# WirelessTRV.net
KiCad netlist of a schematic drawn in EAGLE
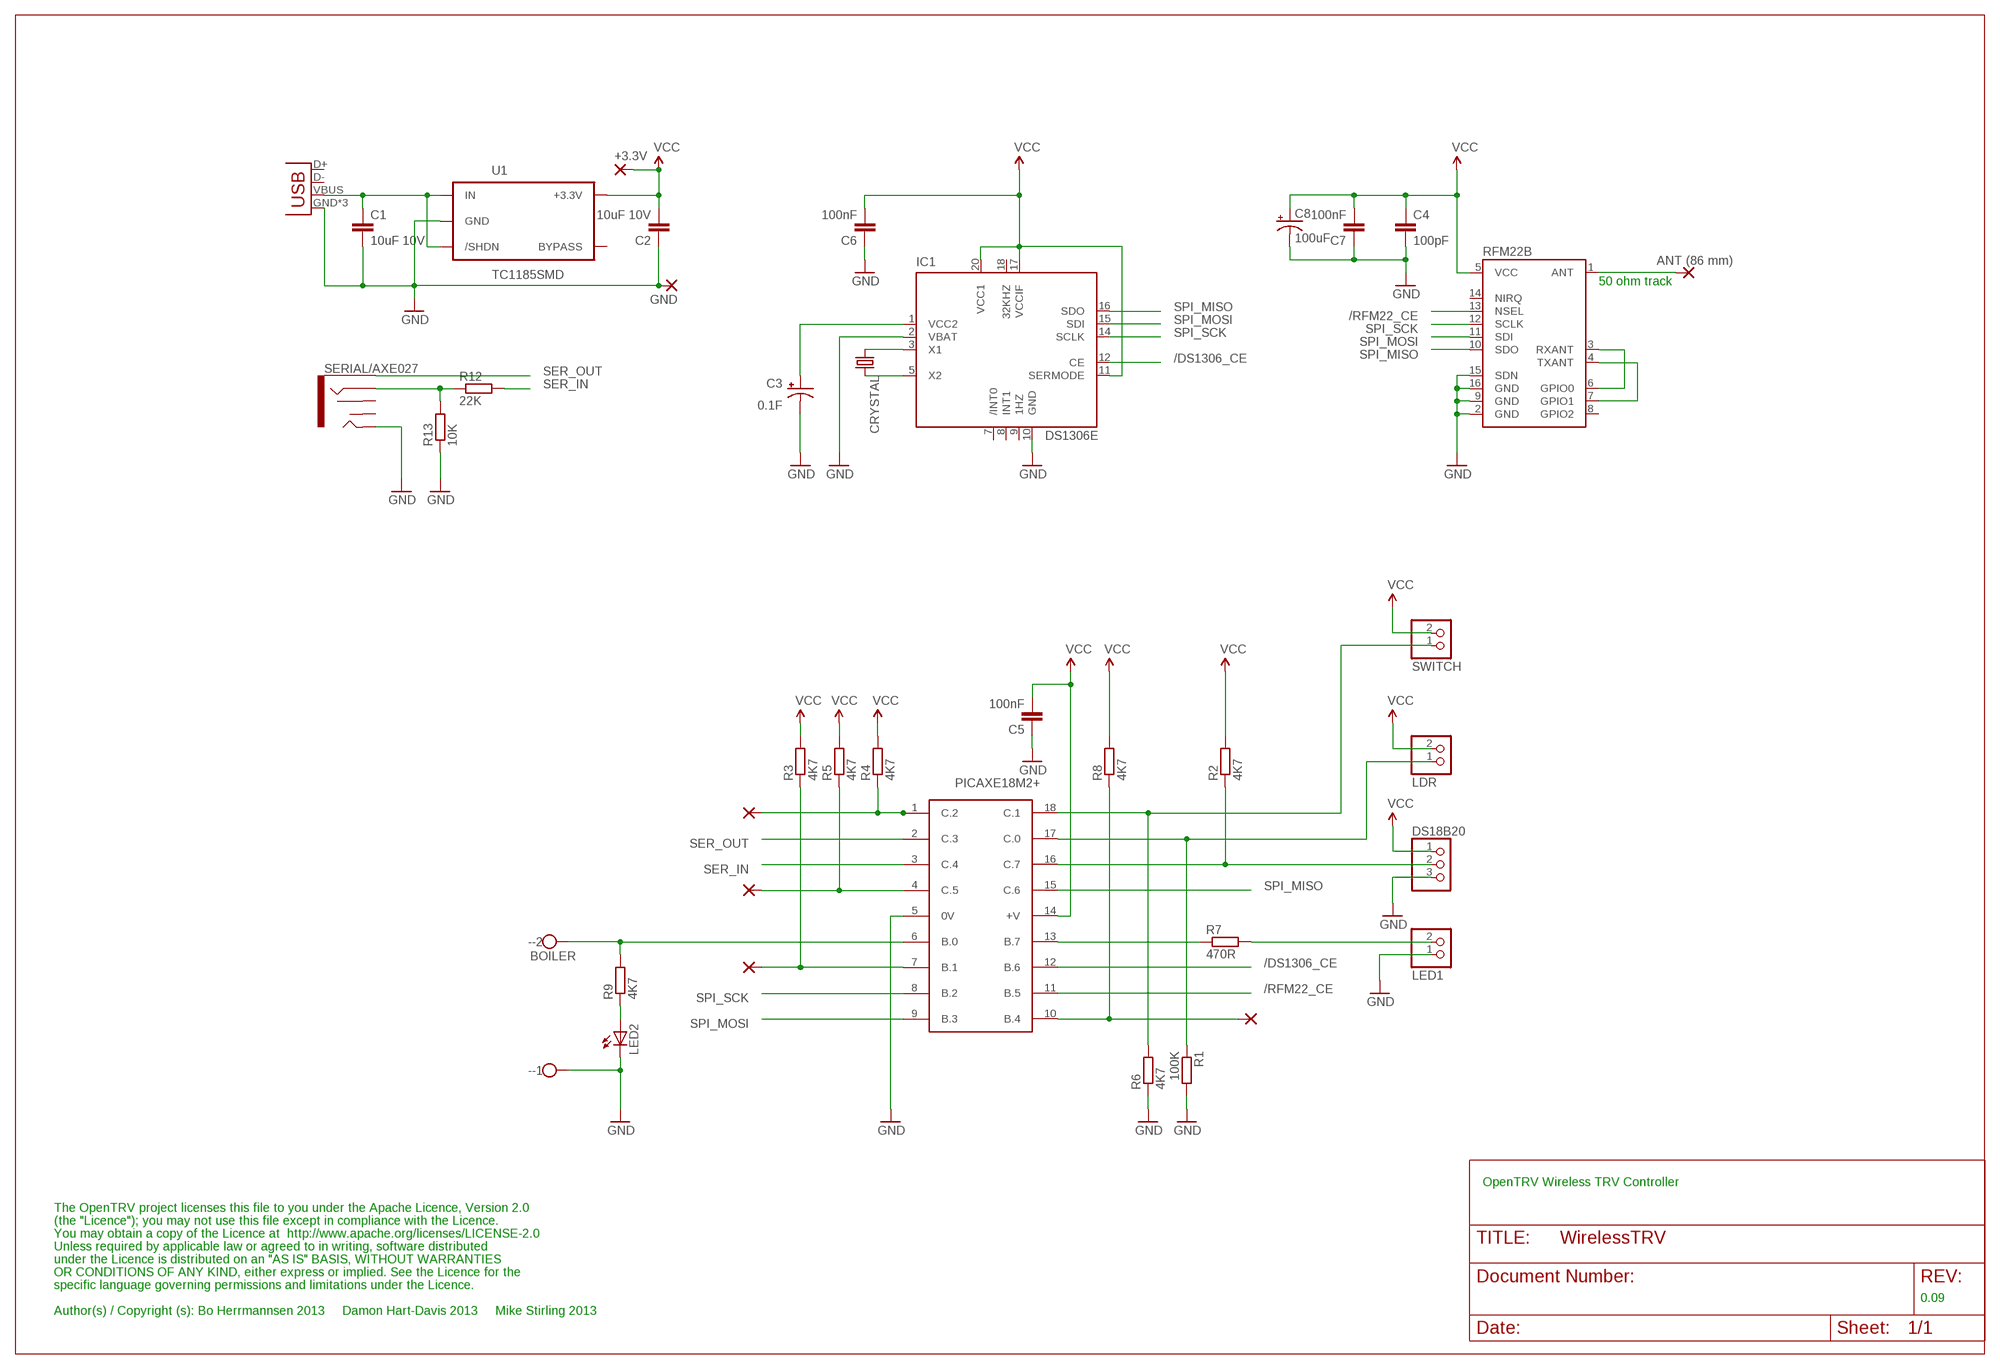
[diagram p0: schematic, sheet 1]

(export (version "E")
  (design (tool "Eeschema 10.0.6"))
  (components
    (comp (ref "+3.3V")
      (value "2,15/1,0")
      (footprint "eagle-import:2,15_1,0")
      (libsource (lib "eagle-import") (part "2,15/1,0"))
    )
    (comp (ref "-")
      (value "BOILER")
      (footprint "eagle-import:W237-102")
      (fields (field (name "MPN") "237-102"))
      (libsource (lib "eagle-import") (part "W237-102"))
    )
    (comp (ref "1")
      (value "2,15/1,0")
      (footprint "eagle-import:2,15_1,0")
      (libsource (lib "eagle-import") (part "2,15/1,0"))
    )
    (comp (ref "4")
      (value "2,15/1,0")
      (footprint "eagle-import:2,15_1,0")
      (libsource (lib "eagle-import") (part "2,15/1,0"))
    )
    (comp (ref "5V")
      (value "USB-MICROB")
      (footprint "eagle-import:USB-MICROB")
      (libsource (lib "eagle-import") (part "USB-MICROB"))
    )
    (comp (ref "7")
      (value "2,15/1,0")
      (footprint "eagle-import:2,15_1,0")
      (libsource (lib "eagle-import") (part "2,15/1,0"))
    )
    (comp (ref "10")
      (value "2,15/1,0")
      (footprint "eagle-import:2,15_1,0")
      (libsource (lib "eagle-import") (part "2,15/1,0"))
    )
    (comp (ref "ANT")
      (value "ANT (86 mm)")
      (footprint "eagle-import:2,15_1,0")
      (libsource (lib "eagle-import") (part "2,15/1,0"))
    )
    (comp (ref "C1")
      (value "10uF 10V")
      (footprint "eagle-import:0603-CAP")
      (libsource (lib "eagle-import") (part "CAP0603-CAP"))
    )
    (comp (ref "C2")
      (value "10uF 10V")
      (footprint "eagle-import:0603-CAP")
      (libsource (lib "eagle-import") (part "CAP0603-CAP"))
    )
    (comp (ref "C3")
      (value "0.1F")
      (footprint "eagle-import:SUPERCAP3.6V")
      (libsource (lib "eagle-import") (part "SUPERCAP3.6VSUPERCAP3.6V"))
    )
    (comp (ref "C4")
      (value "100pF")
      (footprint "eagle-import:0603-CAP")
      (libsource (lib "eagle-import") (part "CAP0603-CAP"))
    )
    (comp (ref "C5")
      (value "100nF")
      (footprint "eagle-import:0603-CAP")
      (libsource (lib "eagle-import") (part "CAP0603-CAP"))
    )
    (comp (ref "C6")
      (value "100nF")
      (footprint "eagle-import:0603-CAP")
      (libsource (lib "eagle-import") (part "CAP0603-CAP"))
    )
    (comp (ref "C7")
      (value "100nF")
      (footprint "eagle-import:0603-CAP")
      (libsource (lib "eagle-import") (part "CAP0603-CAP"))
    )
    (comp (ref "C8")
      (value "100uF")
      (footprint "eagle-import:EIA3216")
      (libsource (lib "eagle-import") (part "CAP_POL1206"))
    )
    (comp (ref "CRYSTAL")
      (value "MC-306")
      (footprint "eagle-import:MC-306")
      (fields (field (name "MPN") "MC-306 60.0KHZ  100PPM ,12.5PF"))
      (libsource (lib "eagle-import") (part "MC-306"))
    )
    (comp (ref "DS18B20")
      (value "PINHD-1X3")
      (footprint "eagle-import:1X03")
      (libsource (lib "eagle-import") (part "PINHD-1X3"))
    )
    (comp (ref "GND")
      (value "2,15/1,0")
      (footprint "eagle-import:2,15_1,0")
      (libsource (lib "eagle-import") (part "2,15/1,0"))
    )
    (comp (ref "IC1")
      (value "DS1306E")
      (footprint "eagle-import:TSSOP20")
      (libsource (lib "eagle-import") (part "DS1306E"))
    )
    (comp (ref "LDR")
      (value "PINHD-1X2")
      (footprint "eagle-import:1X02")
      (libsource (lib "eagle-import") (part "PINHD-1X2"))
    )
    (comp (ref "LED1")
      (value "PINHD-1X2")
      (footprint "eagle-import:1X02")
      (libsource (lib "eagle-import") (part "PINHD-1X2"))
    )
    (comp (ref "LED2")
      (value "LED2012")
      (footprint "eagle-import:LED2012")
      (libsource (lib "eagle-import") (part "LED2012"))
    )
    (comp (ref "PICAXE18M2+")
      (value "PICAXE18M2SO")
      (footprint "eagle-import:SO-18W")
      (libsource (lib "eagle-import") (part "PICAXE18M2SO"))
    )
    (comp (ref "R1")
      (value "100K")
      (footprint "eagle-import:R0603")
      (libsource (lib "eagle-import") (part "R-EU_R0603"))
    )
    (comp (ref "R2")
      (value "4K7")
      (footprint "eagle-import:R0603")
      (libsource (lib "eagle-import") (part "R-EU_R0603"))
    )
    (comp (ref "R3")
      (value "4K7")
      (footprint "eagle-import:R0603")
      (libsource (lib "eagle-import") (part "R-EU_R0603"))
    )
    (comp (ref "R4")
      (value "4K7")
      (footprint "eagle-import:R0603")
      (libsource (lib "eagle-import") (part "R-EU_R0603"))
    )
    (comp (ref "R5")
      (value "4K7")
      (footprint "eagle-import:R0603")
      (libsource (lib "eagle-import") (part "R-EU_R0603"))
    )
    (comp (ref "R6")
      (value "4K7")
      (footprint "eagle-import:R0603")
      (libsource (lib "eagle-import") (part "R-EU_R0603"))
    )
    (comp (ref "R7")
      (value "470R")
      (footprint "eagle-import:R0603")
      (libsource (lib "eagle-import") (part "R-EU_R0603"))
    )
    (comp (ref "R8")
      (value "4K7")
      (footprint "eagle-import:R0603")
      (libsource (lib "eagle-import") (part "R-EU_R0603"))
    )
    (comp (ref "R9")
      (value "4K7")
      (footprint "eagle-import:R0603")
      (libsource (lib "eagle-import") (part "R-EU_R0603"))
    )
    (comp (ref "R12")
      (value "22K")
      (footprint "eagle-import:R0603")
      (libsource (lib "eagle-import") (part "R-EU_R0603"))
    )
    (comp (ref "R13")
      (value "10K")
      (footprint "eagle-import:R0603")
      (libsource (lib "eagle-import") (part "R-EU_R0603"))
    )
    (comp (ref "RFM22B")
      (value "RFM22SMD")
      (footprint "eagle-import:RFM22-XXX-S2")
      (libsource (lib "eagle-import") (part "RFM22SMD"))
    )
    (comp (ref "SERIAL/AXE027")
      (value "AUDIO-JACK2SMD")
      (footprint "eagle-import:AUDIO-JACK-3.5MM-SMD")
      (libsource (lib "eagle-import") (part "AUDIO-JACK2SMD"))
    )
    (comp (ref "SWITCH")
      (value "PINHD-1X2")
      (footprint "eagle-import:1X02")
      (libsource (lib "eagle-import") (part "PINHD-1X2"))
    )
    (comp (ref "U1")
      (value "TC1185SMD")
      (footprint "eagle-import:TC1185")
      (libsource (lib "eagle-import") (part "TC1185SMD"))
    )
  )
  (nets
    (net (code "1") (name "/SER_IN") (class "Default")
      (node (ref "PICAXE18M2+") (pin "3") (pinfunction "C.4_3") (pintype "bidirectional"))
      (node (ref "R12") (pin "2") (pinfunction "2_2") (pintype "passive"))
    )
    (net (code "2") (name "/SER_OUT") (class "Default")
      (node (ref "PICAXE18M2+") (pin "2") (pinfunction "C.3_2") (pintype "bidirectional"))
      (node (ref "SERIAL/AXE027") (pin "SLEEVE") (pinfunction "SLEEVE_SLEEVE") (pintype "bidirectional"))
    )
    (net (code "3") (name "/SPI_MISO") (class "Default")
      (node (ref "IC1") (pin "16") (pinfunction "SDO_16") (pintype "output"))
      (node (ref "PICAXE18M2+") (pin "15") (pinfunction "C.6_15") (pintype "bidirectional"))
      (node (ref "RFM22B") (pin "10") (pinfunction "SDO_10") (pintype "output"))
    )
    (net (code "4") (name "/SPI_MOSI") (class "Default")
      (node (ref "IC1") (pin "15") (pinfunction "SDI_15") (pintype "input"))
      (node (ref "PICAXE18M2+") (pin "9") (pinfunction "B.3_9") (pintype "bidirectional"))
      (node (ref "RFM22B") (pin "11") (pinfunction "SDI_11") (pintype "input"))
    )
    (net (code "5") (name "/SPI_SCK") (class "Default")
      (node (ref "IC1") (pin "14") (pinfunction "SCLK_14") (pintype "input"))
      (node (ref "PICAXE18M2+") (pin "8") (pinfunction "B.2_8") (pintype "bidirectional"))
      (node (ref "RFM22B") (pin "12") (pinfunction "SCLK_12") (pintype "input"))
    )
    (net (code "6") (name "/{slash}DS1306_CE") (class "Default")
      (node (ref "IC1") (pin "12") (pinfunction "CE_12") (pintype "input"))
      (node (ref "PICAXE18M2+") (pin "12") (pinfunction "B.6_12") (pintype "bidirectional"))
    )
    (net (code "7") (name "/{slash}RFM22_CE") (class "Default")
      (node (ref "PICAXE18M2+") (pin "11") (pinfunction "B.5_11") (pintype "bidirectional"))
      (node (ref "RFM22B") (pin "13") (pinfunction "NSEL_13") (pintype "input"))
    )
    (net (code "8") (name "GND") (class "Default")
      (node (ref "-") (pin "1") (pinfunction "KL_1") (pintype "passive"))
      (node (ref "5V") (pin "GND") (pinfunction "GND_GND") (pintype "bidirectional"))
      (node (ref "5V") (pin "MT1") (pinfunction "GND_MT1") (pintype "bidirectional"))
      (node (ref "5V") (pin "MT2") (pinfunction "GND_MT2") (pintype "bidirectional"))
      (node (ref "C1") (pin "2") (pinfunction "2_2") (pintype "passive"))
      (node (ref "C2") (pin "1") (pinfunction "1_1") (pintype "passive"))
      (node (ref "C3") (pin "-") (pinfunction "-_-") (pintype "passive"))
      (node (ref "C4") (pin "2") (pinfunction "2_2") (pintype "passive"))
      (node (ref "C5") (pin "1") (pinfunction "1_1") (pintype "passive"))
      (node (ref "C6") (pin "1") (pinfunction "1_1") (pintype "passive"))
      (node (ref "C7") (pin "1") (pinfunction "1_1") (pintype "passive"))
      (node (ref "C8") (pin "C") (pinfunction "-_C") (pintype "passive"))
      (node (ref "DS18B20") (pin "3") (pinfunction "3_3") (pintype "passive"))
      (node (ref "GND") (pin "1") (pinfunction "P_1") (pintype "passive"))
      (node (ref "IC1") (pin "10") (pinfunction "GND_10") (pintype "power_in"))
      (node (ref "IC1") (pin "2") (pinfunction "VBAT_2") (pintype "power_in"))
      (node (ref "LED1") (pin "1") (pinfunction "1_1") (pintype "passive"))
      (node (ref "LED2") (pin "2") (pinfunction "C_2") (pintype "passive"))
      (node (ref "PICAXE18M2+") (pin "5") (pinfunction "0V_5") (pintype "power_in"))
      (node (ref "R1") (pin "2") (pinfunction "2_2") (pintype "passive"))
      (node (ref "R13") (pin "1") (pinfunction "1_1") (pintype "passive"))
      (node (ref "R6") (pin "1") (pinfunction "1_1") (pintype "passive"))
      (node (ref "RFM22B") (pin "15") (pinfunction "SDN_15") (pintype "input"))
      (node (ref "RFM22B") (pin "16") (pinfunction "GND_16") (pintype "power_in"))
      (node (ref "RFM22B") (pin "2") (pinfunction "GND_2") (pintype "power_in"))
      (node (ref "RFM22B") (pin "9") (pinfunction "GND_9") (pintype "power_in"))
      (node (ref "SERIAL/AXE027") (pin "TIP") (pinfunction "TIP_TIP") (pintype "bidirectional"))
      (node (ref "U1") (pin "2") (pinfunction "GND_2") (pintype "passive"))
    )
    (net (code "9") (name "Net-(-B-KL)") (class "Default")
      (node (ref "-") (pin "2") (pinfunction "KL_2") (pintype "passive"))
      (node (ref "PICAXE18M2+") (pin "6") (pinfunction "B.0_6") (pintype "bidirectional"))
      (node (ref "R9") (pin "2") (pinfunction "2_2") (pintype "passive"))
    )
    (net (code "10") (name "Net-(1-P)") (class "Default")
      (node (ref "1") (pin "1") (pinfunction "P_1") (pintype "passive"))
      (node (ref "PICAXE18M2+") (pin "1") (pinfunction "C.2_1") (pintype "bidirectional"))
      (node (ref "R4") (pin "1") (pinfunction "1_1") (pintype "passive"))
    )
    (net (code "11") (name "Net-(4-P)") (class "Default")
      (node (ref "4") (pin "1") (pinfunction "P_1") (pintype "passive"))
      (node (ref "PICAXE18M2+") (pin "4") (pinfunction "C.5_4") (pintype "bidirectional"))
      (node (ref "R5") (pin "1") (pinfunction "1_1") (pintype "passive"))
    )
    (net (code "12") (name "Net-(7-P)") (class "Default")
      (node (ref "7") (pin "1") (pinfunction "P_1") (pintype "passive"))
      (node (ref "PICAXE18M2+") (pin "7") (pinfunction "B.1_7") (pintype "bidirectional"))
      (node (ref "R3") (pin "1") (pinfunction "1_1") (pintype "passive"))
    )
    (net (code "13") (name "Net-(10-P)") (class "Default")
      (node (ref "10") (pin "1") (pinfunction "P_1") (pintype "passive"))
      (node (ref "PICAXE18M2+") (pin "10") (pinfunction "B.4_10") (pintype "bidirectional"))
      (node (ref "R8") (pin "1") (pinfunction "1_1") (pintype "passive"))
    )
    (net (code "14") (name "Net-(ANT-P)") (class "Default")
      (node (ref "ANT") (pin "1") (pinfunction "P_1") (pintype "passive"))
      (node (ref "RFM22B") (pin "1") (pinfunction "ANT_1") (pintype "bidirectional"))
    )
    (net (code "15") (name "Net-(CRYSTAL-2)") (class "Default")
      (node (ref "CRYSTAL") (pin "4") (pinfunction "2_4") (pintype "passive"))
      (node (ref "IC1") (pin "5") (pinfunction "X2_5") (pintype "input"))
    )
    (net (code "16") (name "Net-(IC1-VCC2)") (class "Default")
      (node (ref "C3") (pin "+") (pinfunction "+_+") (pintype "passive"))
      (node (ref "IC1") (pin "1") (pinfunction "VCC2_1") (pintype "power_in"))
    )
    (net (code "17") (name "Net-(IC1-X1)") (class "Default")
      (node (ref "CRYSTAL") (pin "1") (pinfunction "1_1") (pintype "passive"))
      (node (ref "IC1") (pin "3") (pinfunction "X1_3") (pintype "input"))
    )
    (net (code "18") (name "Net-(LED1-Pad2)") (class "Default")
      (node (ref "LED1") (pin "2") (pinfunction "2_2") (pintype "passive"))
      (node (ref "R7") (pin "2") (pinfunction "2_2") (pintype "passive"))
    )
    (net (code "19") (name "Net-(LED2-A)") (class "Default")
      (node (ref "LED2") (pin "1") (pinfunction "A_1") (pintype "passive"))
      (node (ref "R9") (pin "1") (pinfunction "1_1") (pintype "passive"))
    )
    (net (code "20") (name "Net-(PICAXE18M2+-B.7)") (class "Default")
      (node (ref "PICAXE18M2+") (pin "13") (pinfunction "B.7_13") (pintype "bidirectional"))
      (node (ref "R7") (pin "1") (pinfunction "1_1") (pintype "passive"))
    )
    (net (code "21") (name "Net-(PICAXE18M2+-C.0)") (class "Default")
      (node (ref "LDR") (pin "1") (pinfunction "1_1") (pintype "passive"))
      (node (ref "PICAXE18M2+") (pin "17") (pinfunction "C.0_17") (pintype "bidirectional"))
      (node (ref "R1") (pin "1") (pinfunction "1_1") (pintype "passive"))
    )
    (net (code "22") (name "Net-(PICAXE18M2+-C.1)") (class "Default")
      (node (ref "PICAXE18M2+") (pin "18") (pinfunction "C.1_18") (pintype "bidirectional"))
      (node (ref "R6") (pin "2") (pinfunction "2_2") (pintype "passive"))
      (node (ref "SWITCH") (pin "1") (pinfunction "1_1") (pintype "passive"))
    )
    (net (code "23") (name "Net-(PICAXE18M2+-C.7)") (class "Default")
      (node (ref "DS18B20") (pin "2") (pinfunction "2_2") (pintype "passive"))
      (node (ref "PICAXE18M2+") (pin "16") (pinfunction "C.7_16") (pintype "bidirectional"))
      (node (ref "R2") (pin "1") (pinfunction "1_1") (pintype "passive"))
    )
    (net (code "24") (name "Net-(R12-Pad1)") (class "Default")
      (node (ref "R12") (pin "1") (pinfunction "1_1") (pintype "passive"))
      (node (ref "R13") (pin "2") (pinfunction "2_2") (pintype "passive"))
      (node (ref "SERIAL/AXE027") (pin "RING") (pinfunction "RING_RING") (pintype "bidirectional"))
    )
    (net (code "25") (name "Net-(RFM22B-GPIO0)") (class "Default")
      (node (ref "RFM22B") (pin "3") (pinfunction "RXANT_3") (pintype "input"))
      (node (ref "RFM22B") (pin "6") (pinfunction "GPIO0_6") (pintype "bidirectional"))
    )
    (net (code "26") (name "Net-(RFM22B-GPIO1)") (class "Default")
      (node (ref "RFM22B") (pin "4") (pinfunction "TXANT_4") (pintype "input"))
      (node (ref "RFM22B") (pin "7") (pinfunction "GPIO1_7") (pintype "bidirectional"))
    )
    (net (code "27") (name "Net-(U1-IN)") (class "Default")
      (node (ref "5V") (pin "VBUS") (pinfunction "VBUS_VBUS") (pintype "bidirectional"))
      (node (ref "C1") (pin "1") (pinfunction "1_1") (pintype "passive"))
      (node (ref "U1") (pin "1") (pinfunction "IN_1") (pintype "passive"))
      (node (ref "U1") (pin "3") (pinfunction "/SHDN_3") (pintype "passive"))
    )
    (net (code "28") (name "VCC") (class "Default")
      (node (ref "+3.3V") (pin "1") (pinfunction "P_1") (pintype "passive"))
      (node (ref "C2") (pin "2") (pinfunction "2_2") (pintype "passive"))
      (node (ref "C4") (pin "1") (pinfunction "1_1") (pintype "passive"))
      (node (ref "C5") (pin "2") (pinfunction "2_2") (pintype "passive"))
      (node (ref "C6") (pin "2") (pinfunction "2_2") (pintype "passive"))
      (node (ref "C7") (pin "2") (pinfunction "2_2") (pintype "passive"))
      (node (ref "C8") (pin "A") (pinfunction "+_A") (pintype "passive"))
      (node (ref "DS18B20") (pin "1") (pinfunction "1_1") (pintype "passive"))
      (node (ref "IC1") (pin "11") (pinfunction "SERMODE_11") (pintype "input"))
      (node (ref "IC1") (pin "17") (pinfunction "VCCIF_17") (pintype "power_in"))
      (node (ref "IC1") (pin "20") (pinfunction "VCC1_20") (pintype "power_in"))
      (node (ref "LDR") (pin "2") (pinfunction "2_2") (pintype "passive"))
      (node (ref "PICAXE18M2+") (pin "14") (pinfunction "+V_14") (pintype "power_in"))
      (node (ref "R2") (pin "2") (pinfunction "2_2") (pintype "passive"))
      (node (ref "R3") (pin "2") (pinfunction "2_2") (pintype "passive"))
      (node (ref "R4") (pin "2") (pinfunction "2_2") (pintype "passive"))
      (node (ref "R5") (pin "2") (pinfunction "2_2") (pintype "passive"))
      (node (ref "R8") (pin "2") (pinfunction "2_2") (pintype "passive"))
      (node (ref "RFM22B") (pin "5") (pinfunction "VCC_5") (pintype "bidirectional"))
      (node (ref "SWITCH") (pin "2") (pinfunction "2_2") (pintype "passive"))
      (node (ref "U1") (pin "5") (pinfunction "+3.3V_5") (pintype "power_in"))
    )
    (net (code "29") (name "unconnected-(5V-PadD+)") (class "Default")
      (node (ref "5V") (pin "D+") (pinfunction "D+_D+") (pintype "bidirectional"))
    )
    (net (code "30") (name "unconnected-(5V-PadD-)") (class "Default")
      (node (ref "5V") (pin "D-") (pinfunction "D-_D-") (pintype "bidirectional"))
    )
    (net (code "31") (name "unconnected-(IC1-1HZ-Pad9)") (class "Default")
      (node (ref "IC1") (pin "9") (pinfunction "1HZ_9") (pintype "output"))
    )
    (net (code "32") (name "unconnected-(IC1-32KHZ-Pad18)") (class "Default")
      (node (ref "IC1") (pin "18") (pinfunction "32KHZ_18") (pintype "output"))
    )
    (net (code "33") (name "unconnected-(IC1-INT1-Pad8)") (class "Default")
      (node (ref "IC1") (pin "8") (pinfunction "INT1_8") (pintype "output"))
    )
    (net (code "34") (name "unconnected-(IC1-{slash}INT0-Pad7)") (class "Default")
      (node (ref "IC1") (pin "7") (pinfunction "/INT0_7") (pintype "output"))
    )
    (net (code "35") (name "unconnected-(RFM22B-GPIO2-Pad8)") (class "Default")
      (node (ref "RFM22B") (pin "8") (pinfunction "GPIO2_8") (pintype "bidirectional"))
    )
    (net (code "36") (name "unconnected-(RFM22B-NIRQ-Pad14)") (class "Default")
      (node (ref "RFM22B") (pin "14") (pinfunction "NIRQ_14") (pintype "output"))
    )
    (net (code "37") (name "unconnected-(SERIAL/AXE027-PadRSH)") (class "Default")
      (node (ref "SERIAL/AXE027") (pin "RSH") (pinfunction "RSH_RSH") (pintype "bidirectional"))
    )
    (net (code "38") (name "unconnected-(SERIAL/AXE027-PadTSH)") (class "Default")
      (node (ref "SERIAL/AXE027") (pin "TSH") (pinfunction "TSH_TSH") (pintype "bidirectional"))
    )
    (net (code "39") (name "unconnected-(U1-BYPASS-Pad4)") (class "Default")
      (node (ref "U1") (pin "4") (pinfunction "BYPASS_4") (pintype "passive"))
    )
  )
)
